# stm32_motordrive.net
KiCad netlist of a schematic drawn in EasyEDA Pro
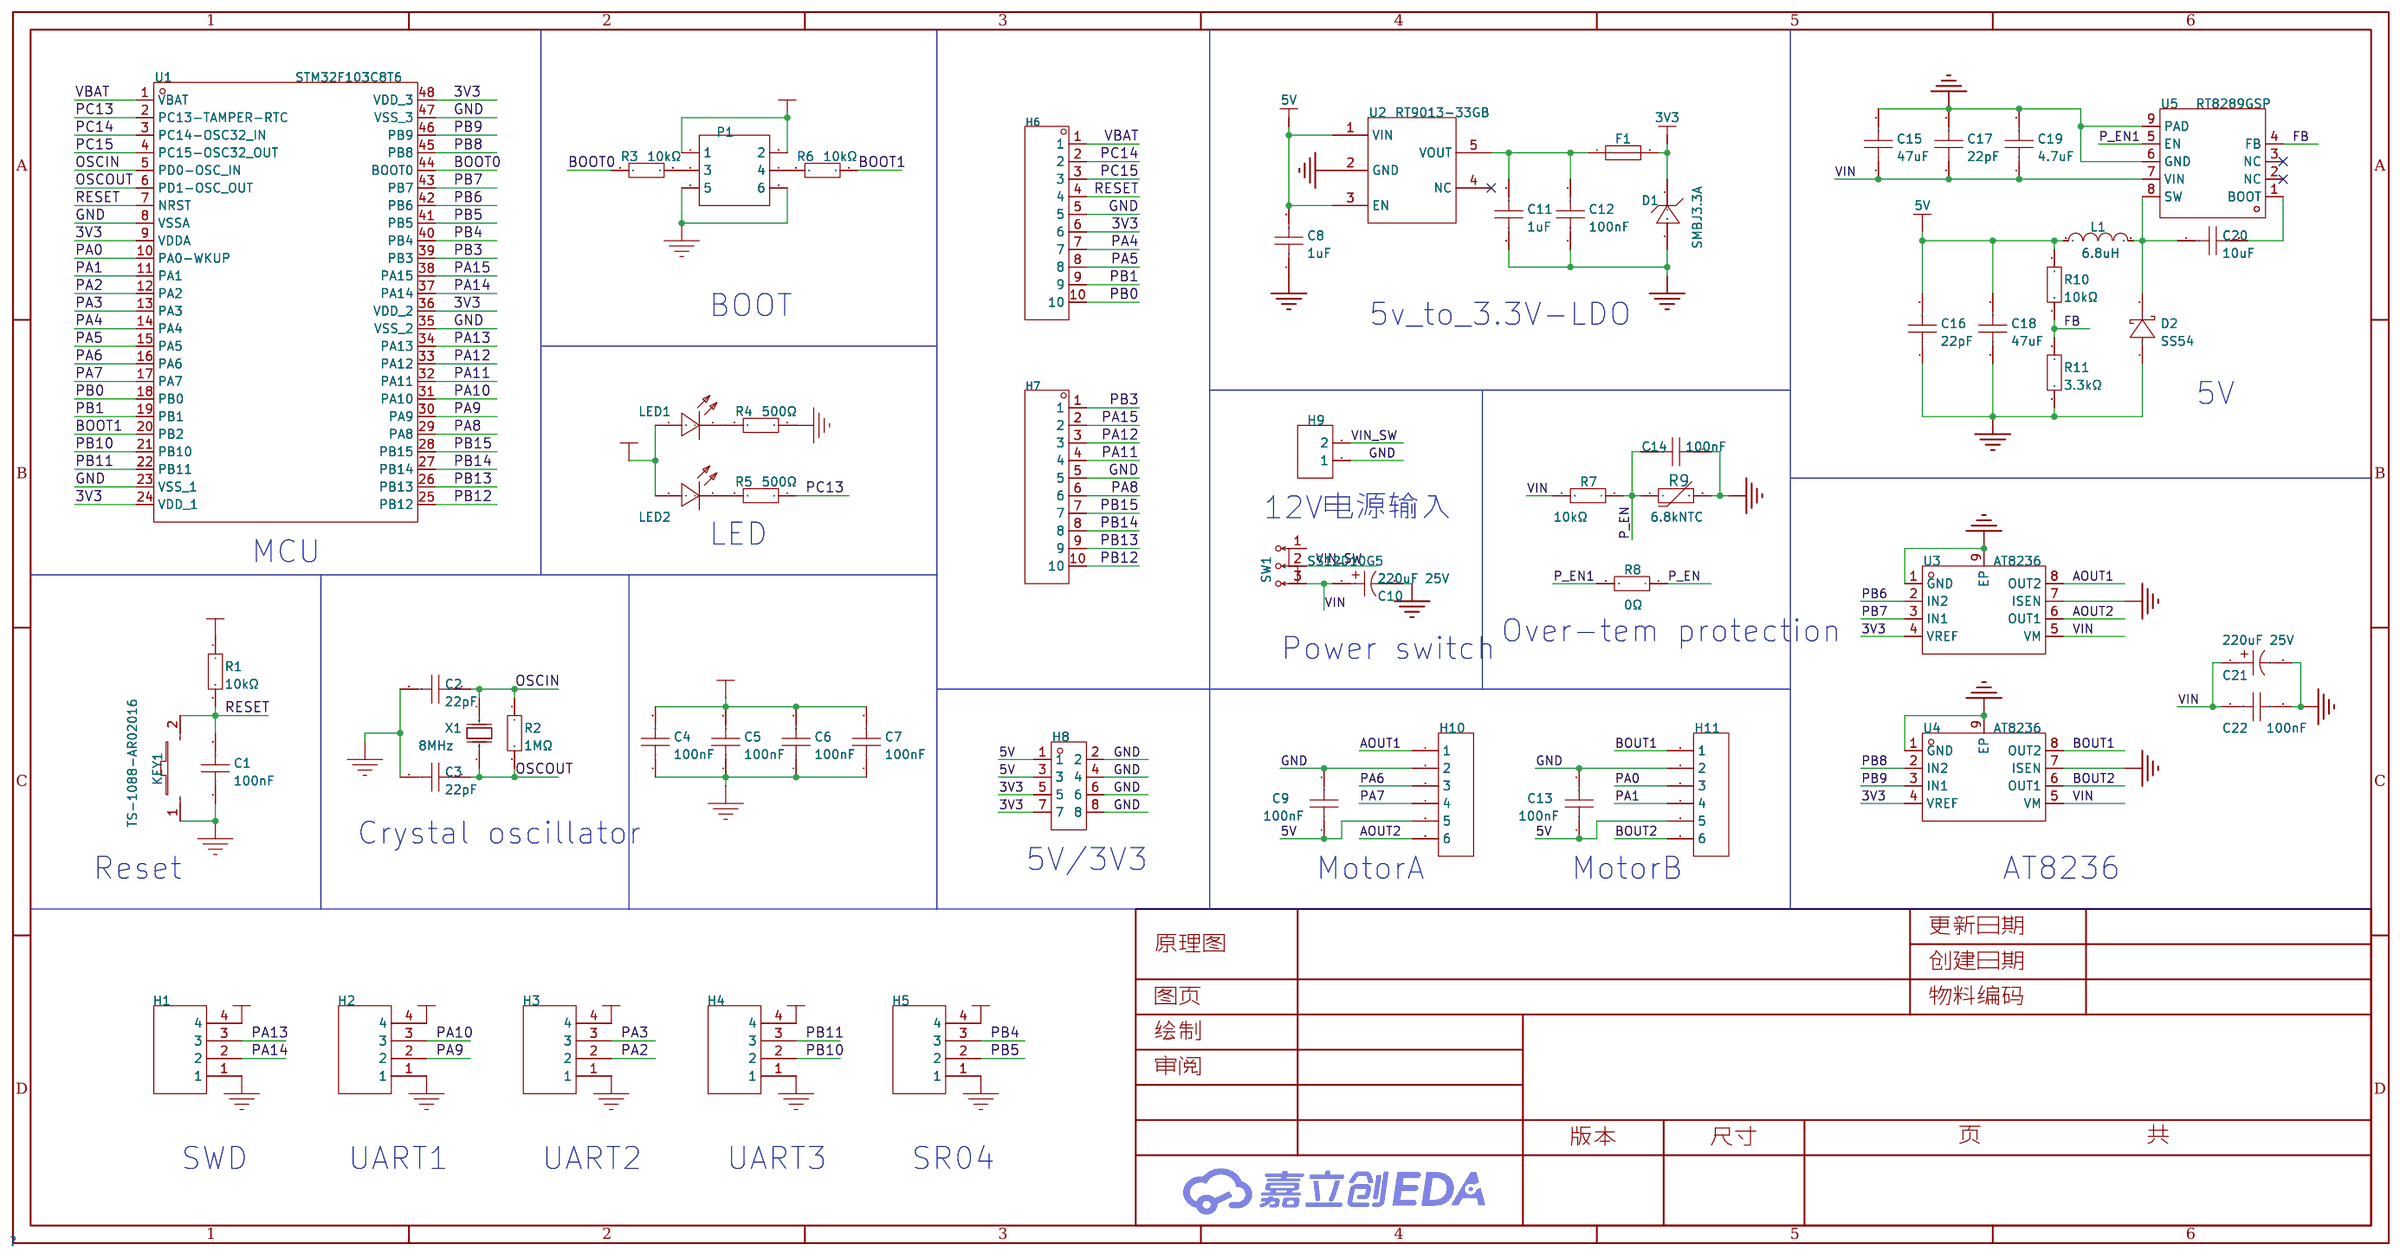
[diagram p0: schematic sheet]

(export (version "E")
  (design (tool "Eeschema 10.0.6"))
  (components
    (comp (ref "C1")
      (value "100nF")
      (fields
        (field (name "Manufacturer Part") "CC0603KRX7R9BB104")
        (field (name "Manufacturer") "YAGEO(国巨)")
      )
      (libsource (lib "easyedapro") (part "104"))
    )
    (comp (ref "C2")
      (value "22pF")
      (fields
        (field (name "Manufacturer Part") "CC0603JRNPO9BN220")
        (field (name "Manufacturer") "YAGEO(国巨)")
      )
      (libsource (lib "easyedapro") (part "22P"))
    )
    (comp (ref "C3")
      (value "22pF")
      (fields
        (field (name "Manufacturer Part") "CC0603JRNPO9BN220")
        (field (name "Manufacturer") "YAGEO(国巨)")
      )
      (libsource (lib "easyedapro") (part "22P"))
    )
    (comp (ref "C4")
      (value "100nF")
      (fields
        (field (name "Manufacturer Part") "CC0603KRX7R9BB104")
        (field (name "Manufacturer") "YAGEO(国巨)")
      )
      (libsource (lib "easyedapro") (part "104"))
    )
    (comp (ref "C5")
      (value "100nF")
      (fields
        (field (name "Manufacturer Part") "CC0603KRX7R9BB104")
        (field (name "Manufacturer") "YAGEO(国巨)")
      )
      (libsource (lib "easyedapro") (part "104"))
    )
    (comp (ref "C6")
      (value "100nF")
      (fields
        (field (name "Manufacturer Part") "CC0603KRX7R9BB104")
        (field (name "Manufacturer") "YAGEO(国巨)")
      )
      (libsource (lib "easyedapro") (part "104"))
    )
    (comp (ref "C7")
      (value "100nF")
      (fields
        (field (name "Manufacturer Part") "CC0603KRX7R9BB104")
        (field (name "Manufacturer") "YAGEO(国巨)")
      )
      (libsource (lib "easyedapro") (part "104"))
    )
    (comp (ref "C8")
      (value "1uF")
      (fields
        (field (name "Manufacturer Part") "CL10A105KB8NNNC")
        (field (name "Manufacturer") "SAMSUNG(三星)")
      )
      (libsource (lib "easyedapro") (part "CapAcitance"))
    )
    (comp (ref "C9")
      (value "100nF")
      (fields
        (field (name "Manufacturer Part") "CC0603KRX7R9BB104")
        (field (name "Manufacturer") "YAGEO(国巨)")
      )
      (libsource (lib "easyedapro") (part "CapAcitance"))
    )
    (comp (ref "C10")
      (value "220uF 25V")
      (footprint "easyedapro:CAP-SMD_BD6.3-L6.6-W6.6-LS7.2-FD")
      (description "容值:220uF;精度:±20%;额定电压:25V;纹波电流:165mA@120Hz;等效串联电阻:-;")
      (fields (field (name "Manufacturer Part") "RST220UF25V019") (field (name "Manufacturer") "KNSCHA(科尼盛)"))
      (libsource (lib "easyedapro") (part "RST220UF25V019"))
    )
    (comp (ref "C11")
      (value "1uF")
      (fields
        (field (name "Manufacturer Part") "CL10A105KB8NNNC")
        (field (name "Manufacturer") "SAMSUNG(三星)")
      )
      (libsource (lib "easyedapro") (part "CapAcitance"))
    )
    (comp (ref "C12")
      (value "100nF")
      (fields
        (field (name "Manufacturer Part") "CC0603KRX7R9BB104")
        (field (name "Manufacturer") "YAGEO(国巨)")
      )
      (libsource (lib "easyedapro") (part "CapAcitance"))
    )
    (comp (ref "C13")
      (value "100nF")
      (fields
        (field (name "Manufacturer Part") "CC0603KRX7R9BB104")
        (field (name "Manufacturer") "YAGEO(国巨)")
      )
      (libsource (lib "easyedapro") (part "CapAcitance"))
    )
    (comp (ref "C14")
      (value "100nF")
      (fields
        (field (name "Manufacturer Part") "CC0603KRX7R9BB104")
        (field (name "Manufacturer") "YAGEO(国巨)")
      )
      (libsource (lib "easyedapro") (part "CapAcitance"))
    )
    (comp (ref "C15")
      (value "47uF")
      (fields
        (field (name "Manufacturer Part") "CL10A476MQ8QRNC")
        (field (name "Manufacturer") "SAMSUNG(三星)")
      )
      (libsource (lib "easyedapro") (part "CapAcitance"))
    )
    (comp (ref "C16")
      (value "22pF")
      (fields
        (field (name "Manufacturer Part") "CC0603JRNPO9BN220")
        (field (name "Manufacturer") "YAGEO(国巨)")
      )
      (libsource (lib "easyedapro") (part "CapAcitance"))
    )
    (comp (ref "C17")
      (value "22pF")
      (fields
        (field (name "Manufacturer Part") "CC0603JRNPO9BN220")
        (field (name "Manufacturer") "YAGEO(国巨)")
      )
      (libsource (lib "easyedapro") (part "CapAcitance"))
    )
    (comp (ref "C18")
      (value "47uF")
      (fields
        (field (name "Manufacturer Part") "CL10A476MQ8QRNC")
        (field (name "Manufacturer") "SAMSUNG(三星)")
      )
      (libsource (lib "easyedapro") (part "CapAcitance"))
    )
    (comp (ref "C19")
      (value "4.7uF")
      (fields
        (field (name "Manufacturer Part") "CL10A475KP8NNNC")
        (field (name "Manufacturer") "SAMSUNG(三星)")
      )
      (libsource (lib "easyedapro") (part "CapAcitance"))
    )
    (comp (ref "C20")
      (value "10uF")
      (fields
        (field (name "Manufacturer Part") "CL10A106KP8NNNC")
        (field (name "Manufacturer") "SAMSUNG(三星)")
      )
      (libsource (lib "easyedapro") (part "CapAcitance"))
    )
    (comp (ref "C21")
      (value "220uF 25V")
      (footprint "easyedapro:CAP-SMD_BD6.3-L6.6-W6.6-LS7.2-FD")
      (description "容值:220uF;精度:±20%;额定电压:25V;纹波电流:165mA@120Hz;等效串联电阻:-;")
      (fields (field (name "Manufacturer Part") "RST220UF25V019") (field (name "Manufacturer") "KNSCHA(科尼盛)"))
      (libsource (lib "easyedapro") (part "RST220UF25V019"))
    )
    (comp (ref "C22")
      (value "100nF")
      (fields
        (field (name "Manufacturer Part") "CC0603KRX7R9BB104")
        (field (name "Manufacturer") "YAGEO(国巨)")
      )
      (libsource (lib "easyedapro") (part "CapAcitance"))
    )
    (comp (ref "D1")
      (value "SMBJ3.3A")
      (footprint "easyedapro:SMB_L4.6-W3.6-LS5.3-RD")
      (description "反向截止电压(Vrwm):3.3V;最大钳位电压:7.3V;峰值脉冲功率(Ppp)@10/1000us:600W;击穿电压:4.1V;")
      (fields (field (name "Manufacturer") "JKSEMI(金开盛)"))
      (libsource (lib "easyedapro") (part "SMBJ3.3A_C362089"))
    )
    (comp (ref "D2")
      (value "SS54")
      (footprint "easyedapro:SMA_L4.3-W2.6-LS5.0-FD")
      (description "二极管配置:独立式;正向压降(Vf):550mV@5.0A;直流反向耐压(Vr):40V;平均整流电流(Io):5A;")
      (fields (field (name "Manufacturer") "宏迦橙"))
      (libsource (lib "easyedapro") (part "SS54_C7420369"))
    )
    (comp (ref "F1")
      (value "BSMD0603-050-6V")
      (footprint "easyedapro:F0603")
      (description "最大电压:6V;最大电流:40A;保持电流:500mA;跳闸电流:1A;")
      (fields (field (name "Manufacturer") "BHFUSE(佰宏)"))
      (libsource (lib "easyedapro") (part "BSMD0603-050-6V"))
    )
    (comp (ref "H1")
      (value "PZ254V-11-04P")
      (fields (field (name "Manufacturer") "XFCN(兴飞)"))
      (libsource (lib "easyedapro") (part "220S-1*4P H=8.5MM Ytype Gold-plated"))
    )
    (comp (ref "H2")
      (value "PZ254V-11-04P")
      (fields (field (name "Manufacturer") "XFCN(兴飞)"))
      (libsource (lib "easyedapro") (part "220S-1*4P H=8.5MM Ytype Gold-plated"))
    )
    (comp (ref "H3")
      (value "PZ254V-11-04P")
      (fields (field (name "Manufacturer") "XFCN(兴飞)"))
      (libsource (lib "easyedapro") (part "220S-1*4P H=8.5MM Ytype Gold-plated"))
    )
    (comp (ref "H4")
      (value "PZ254V-11-04P")
      (fields (field (name "Manufacturer") "XFCN(兴飞)"))
      (libsource (lib "easyedapro") (part "220S-1*4P H=8.5MM Ytype Gold-plated"))
    )
    (comp (ref "H5")
      (value "PZ254V-11-04P")
      (fields (field (name "Manufacturer") "XFCN(兴飞)"))
      (libsource (lib "easyedapro") (part "220S-1*4P H=8.5MM Ytype Gold-plated"))
    )
    (comp (ref "H6")
      (value "2.54-1*10P针")
      (footprint "easyedapro:HDR-TH_10P-P2.54-V-M-1")
      (fields (field (name "Manufacturer") "BOOMELE(博穆精密)"))
      (libsource (lib "easyedapro") (part "Header-Male-2.54_1x10"))
    )
    (comp (ref "H7")
      (value "2.54-1*10P针")
      (footprint "easyedapro:HDR-TH_10P-P2.54-V-M-1")
      (fields (field (name "Manufacturer") "BOOMELE(博穆精密)"))
      (libsource (lib "easyedapro") (part "Header-Male-2.54_1x10"))
    )
    (comp (ref "H8")
      (value "PZ2.54-2*4")
      (footprint "easyedapro:HDR-TH_8P-P2.54-V-M-R2-C4-S2.54")
      (description "插针结构:2x4P;间距:2.54mm;排数:双排;总PIN位数:8P;")
      (fields (field (name "Manufacturer") "ZHOURI(洲日)"))
      (libsource (lib "easyedapro") (part "PZ2.54-2*4"))
    )
    (comp (ref "H9")
      (value "XY301V-A-5.0-2P")
      (fields (field (name "Manufacturer") "XINLAIYA(新莱亚)"))
      (libsource (lib "easyedapro") (part "Header-Female-2.54_1x2"))
    )
    (comp (ref "H10")
      (value "~")
      (footprint "easyedapro:XH2.54-LI-6P弯针")
      (libsource (lib "easyedapro") (part "XH2.54-LI-6P弯针"))
    )
    (comp (ref "H11")
      (value "~")
      (footprint "easyedapro:XH2.54-LI-6P弯针")
      (libsource (lib "easyedapro") (part "XH2.54-LI-6P弯针"))
    )
    (comp (ref "KEY1")
      (value "TS-1088-AR02016")
      (fields (field (name "Manufacturer") "XUNPU(讯普)"))
      (libsource (lib "easyedapro") (part "Switch3x4x2"))
    )
    (comp (ref "L1")
      (value "6.8uH")
      (fields (field (name "Manufacturer Part") "FXL0630-6R8-M") (field (name "Manufacturer") "cjiang(长江微电)"))
      (libsource (lib "easyedapro") (part "SDFL1608S100KTF"))
    )
    (comp (ref "LED1")
      (value "NCD0805R1")
      (fields (field (name "Manufacturer") "国星光电"))
      (libsource (lib "easyedapro") (part "204-10SURD/S530-A3"))
    )
    (comp (ref "LED2")
      (value "NCD0805R1")
      (fields (field (name "Manufacturer") "国星光电"))
      (libsource (lib "easyedapro") (part "204-10SURD/S530-A3"))
    )
    (comp (ref "P1")
      (value "2.54-2*3P针")
      (fields (field (name "Manufacturer") "BOOMELE(博穆精密)"))
      (libsource (lib "easyedapro") (part "HDR-IDC-2.54-2X3P"))
    )
    (comp (ref "R1")
      (value "10kΩ")
      (fields
        (field (name "Manufacturer Part") "0603WAF1002T5E")
        (field (name "Manufacturer") "UNI-ROYAL(厚声)")
      )
      (libsource (lib "easyedapro") (part "电阻"))
    )
    (comp (ref "R2")
      (value "1MΩ")
      (fields
        (field (name "Manufacturer Part") "0603WAF1004T5E")
        (field (name "Manufacturer") "UNI-ROYAL(厚声)")
      )
      (libsource (lib "easyedapro") (part "电阻"))
    )
    (comp (ref "R3")
      (value "10kΩ")
      (fields
        (field (name "Manufacturer Part") "0603WAF1002T5E")
        (field (name "Manufacturer") "UNI-ROYAL(厚声)")
      )
      (libsource (lib "easyedapro") (part "电阻"))
    )
    (comp (ref "R4")
      (value "500Ω")
      (fields (field (name "Manufacturer Part") "RT0603BRC07500RL") (field (name "Manufacturer") "YAGEO(国巨)"))
      (libsource (lib "easyedapro") (part "电阻"))
    )
    (comp (ref "R5")
      (value "500Ω")
      (fields (field (name "Manufacturer Part") "RT0603BRC07500RL") (field (name "Manufacturer") "YAGEO(国巨)"))
      (libsource (lib "easyedapro") (part "电阻"))
    )
    (comp (ref "R6")
      (value "10kΩ")
      (fields
        (field (name "Manufacturer Part") "0603WAF1002T5E")
        (field (name "Manufacturer") "UNI-ROYAL(厚声)")
      )
      (libsource (lib "easyedapro") (part "电阻"))
    )
    (comp (ref "R7")
      (value "10kΩ")
      (fields (field (name "Manufacturer Part") "RT0603BRD0710KL") (field (name "Manufacturer") "YAGEO(国巨)"))
      (libsource (lib "easyedapro") (part "电阻"))
    )
    (comp (ref "R8")
      (value "0Ω")
      (fields
        (field (name "Manufacturer Part") "0603WAF0000T5E")
        (field (name "Manufacturer") "UNI-ROYAL(厚声)")
      )
      (libsource (lib "easyedapro") (part "电阻"))
    )
    (comp (ref "R9")
      (value "6.8kNTC")
      (footprint "easyedapro:R0603")
      (description "阻值(25°C):6.8kΩ;B值(25°C/50°C):3950K;电阻精度:±5%;功率:100mW;B值精度:±3%;最大稳态电流(25°C):380uA;")
      (fields (field (name "Manufacturer") "muRata(村田)"))
      (libsource (lib "easyedapro") (part "NCP18XW682J03RB"))
    )
    (comp (ref "R10")
      (value "10kΩ")
      (fields (field (name "Manufacturer Part") "RT0603BRD0710KL") (field (name "Manufacturer") "YAGEO(国巨)"))
      (libsource (lib "easyedapro") (part "电阻"))
    )
    (comp (ref "R11")
      (value "3.3kΩ")
      (fields
        (field (name "Manufacturer Part") "0603WAF3301T5E")
        (field (name "Manufacturer") "UNI-ROYAL(厚声)")
      )
      (libsource (lib "easyedapro") (part "电阻"))
    )
    (comp (ref "SW1")
      (value "SS12D10G5")
      (fields (field (name "Manufacturer") "SHOU HAN(首韩)"))
      (libsource (lib "easyedapro") (part "3脚两档开关(SS12D10G4型号）"))
    )
    (comp (ref "U1")
      (value "STM32F103C8T6")
      (fields (field (name "Manufacturer") "ST(意法半导体)"))
      (libsource (lib "easyedapro") (part "STM32F103C8T6"))
    )
    (comp (ref "U2")
      (value "RT9013-33GB")
      (footprint "easyedapro:SOT-23-5_L3.0-W1.7-P0.95-LS2.8-BL")
      (description "输出类型:固定;最大输入电压:5.5V;输出电压:3.3V;最大输出电流:500mA;电源纹波抑制比(PSRR):50dB@(10kHz);输出极性:正极;")
      (fields (field (name "Manufacturer") "RICHTEK(立锜)"))
      (libsource (lib "easyedapro") (part "RT9013-33GB"))
    )
    (comp (ref "U3")
      (value "AT8236")
      (footprint "easyedapro:ESOP-8_L4.9-W3.9-P1.27-LS6.0-BL-EP")
      (fields (field (name "Manufacturer") "杭州中科微"))
      (libsource (lib "easyedapro") (part "AT8236"))
    )
    (comp (ref "U4")
      (value "AT8236")
      (footprint "easyedapro:ESOP-8_L4.9-W3.9-P1.27-LS6.0-BL-EP")
      (fields (field (name "Manufacturer") "杭州中科微"))
      (libsource (lib "easyedapro") (part "AT8236"))
    )
    (comp (ref "U5")
      (value "RT8289GSP")
      (footprint "easyedapro:SOIC-8_L5.0-W4.0-P1.27-LS6.0-BL-EP2.0")
      (description "功能类型:降压型;输出类型:可调;输入电压:5.5V~32V;输出电压:1.222V~26V;输出电流(最大值):5A;")
      (fields (field (name "Manufacturer") "RICHTEK(立锜)"))
      (libsource (lib "easyedapro") (part "RT8289GSP"))
    )
    (comp (ref "X1")
      (value "8MHz")
      (fields (field (name "Manufacturer Part") "X50328MSB2GI") (field (name "Manufacturer") "YXC(扬兴晶振)"))
      (libsource (lib "easyedapro") (part "8MHz"))
    )
  )
  (nets
    (net (code "1") (name "/AOUT1") (class "Default")
      (node (ref "H10") (pin "1") (pinfunction "1_1") (pintype "input"))
      (node (ref "U3") (pin "8") (pinfunction "OUT2_8") (pintype "unspecified"))
    )
    (net (code "2") (name "/AOUT2") (class "Default")
      (node (ref "H10") (pin "6") (pinfunction "6_6") (pintype "input"))
      (node (ref "U3") (pin "6") (pinfunction "OUT1_6") (pintype "unspecified"))
    )
    (net (code "3") (name "/BOOT0") (class "Default")
      (node (ref "R3") (pin "2") (pinfunction "2_2") (pintype "input"))
      (node (ref "U1") (pin "44") (pinfunction "BOOT0_44") (pintype "unspecified"))
    )
    (net (code "4") (name "/BOOT1") (class "Default")
      (node (ref "R6") (pin "1") (pinfunction "1_1") (pintype "input"))
      (node (ref "U1") (pin "20") (pinfunction "PB2_20") (pintype "unspecified"))
    )
    (net (code "5") (name "/BOUT1") (class "Default")
      (node (ref "H11") (pin "1") (pinfunction "1_1") (pintype "input"))
      (node (ref "U4") (pin "8") (pinfunction "OUT2_8") (pintype "unspecified"))
    )
    (net (code "6") (name "/BOUT2") (class "Default")
      (node (ref "H11") (pin "6") (pinfunction "6_6") (pintype "input"))
      (node (ref "U4") (pin "6") (pinfunction "OUT1_6") (pintype "unspecified"))
    )
    (net (code "7") (name "/FB") (class "Default")
      (node (ref "R10") (pin "1") (pinfunction "1_1") (pintype "input"))
      (node (ref "R11") (pin "2") (pinfunction "2_2") (pintype "input"))
      (node (ref "U5") (pin "4") (pinfunction "FB_4") (pintype "unspecified"))
    )
    (net (code "8") (name "/OSCIN") (class "Default")
      (node (ref "C2") (pin "1") (pinfunction "1_1") (pintype "unspecified"))
      (node (ref "R2") (pin "1") (pinfunction "1_1") (pintype "input"))
      (node (ref "U1") (pin "5") (pinfunction "PD0-OSC_IN_5") (pintype "unspecified"))
      (node (ref "X1") (pin "1") (pinfunction "OSC1_1") (pintype "unspecified"))
    )
    (net (code "9") (name "/OSCOUT") (class "Default")
      (node (ref "C3") (pin "1") (pinfunction "1_1") (pintype "unspecified"))
      (node (ref "R2") (pin "2") (pinfunction "2_2") (pintype "input"))
      (node (ref "U1") (pin "6") (pinfunction "PD1-OSC_OUT_6") (pintype "unspecified"))
      (node (ref "X1") (pin "2") (pinfunction "OSC2_2") (pintype "unspecified"))
    )
    (net (code "10") (name "/PA0") (class "Default")
      (node (ref "H11") (pin "3") (pinfunction "3_3") (pintype "input"))
      (node (ref "U1") (pin "10") (pinfunction "PA0-WKUP_10") (pintype "unspecified"))
    )
    (net (code "11") (name "/PA1") (class "Default")
      (node (ref "H11") (pin "4") (pinfunction "4_4") (pintype "input"))
      (node (ref "U1") (pin "11") (pinfunction "PA1_11") (pintype "unspecified"))
    )
    (net (code "12") (name "/PA2") (class "Default")
      (node (ref "H3") (pin "2") (pinfunction "2_2") (pintype "unspecified"))
      (node (ref "U1") (pin "12") (pinfunction "PA2_12") (pintype "unspecified"))
    )
    (net (code "13") (name "/PA3") (class "Default")
      (node (ref "H3") (pin "3") (pinfunction "3_3") (pintype "unspecified"))
      (node (ref "U1") (pin "13") (pinfunction "PA3_13") (pintype "unspecified"))
    )
    (net (code "14") (name "/PA4") (class "Default")
      (node (ref "H6") (pin "7") (pinfunction "7_7") (pintype "input"))
      (node (ref "U1") (pin "14") (pinfunction "PA4_14") (pintype "unspecified"))
    )
    (net (code "15") (name "/PA5") (class "Default")
      (node (ref "H6") (pin "8") (pinfunction "8_8") (pintype "input"))
      (node (ref "U1") (pin "15") (pinfunction "PA5_15") (pintype "unspecified"))
    )
    (net (code "16") (name "/PA6") (class "Default")
      (node (ref "H10") (pin "3") (pinfunction "3_3") (pintype "input"))
      (node (ref "U1") (pin "16") (pinfunction "PA6_16") (pintype "unspecified"))
    )
    (net (code "17") (name "/PA7") (class "Default")
      (node (ref "H10") (pin "4") (pinfunction "4_4") (pintype "input"))
      (node (ref "U1") (pin "17") (pinfunction "PA7_17") (pintype "unspecified"))
    )
    (net (code "18") (name "/PA8") (class "Default")
      (node (ref "H7") (pin "6") (pinfunction "6_6") (pintype "input"))
      (node (ref "U1") (pin "29") (pinfunction "PA8_29") (pintype "unspecified"))
    )
    (net (code "19") (name "/PA9") (class "Default")
      (node (ref "H2") (pin "2") (pinfunction "2_2") (pintype "unspecified"))
      (node (ref "U1") (pin "30") (pinfunction "PA9_30") (pintype "unspecified"))
    )
    (net (code "20") (name "/PA10") (class "Default")
      (node (ref "H2") (pin "3") (pinfunction "3_3") (pintype "unspecified"))
      (node (ref "U1") (pin "31") (pinfunction "PA10_31") (pintype "unspecified"))
    )
    (net (code "21") (name "/PA11") (class "Default")
      (node (ref "H7") (pin "4") (pinfunction "4_4") (pintype "input"))
      (node (ref "U1") (pin "32") (pinfunction "PA11_32") (pintype "unspecified"))
    )
    (net (code "22") (name "/PA12") (class "Default")
      (node (ref "H7") (pin "3") (pinfunction "3_3") (pintype "input"))
      (node (ref "U1") (pin "33") (pinfunction "PA12_33") (pintype "unspecified"))
    )
    (net (code "23") (name "/PA13") (class "Default")
      (node (ref "H1") (pin "3") (pinfunction "3_3") (pintype "unspecified"))
      (node (ref "U1") (pin "34") (pinfunction "PA13_34") (pintype "unspecified"))
    )
    (net (code "24") (name "/PA14") (class "Default")
      (node (ref "H1") (pin "2") (pinfunction "2_2") (pintype "unspecified"))
      (node (ref "U1") (pin "37") (pinfunction "PA14_37") (pintype "unspecified"))
    )
    (net (code "25") (name "/PA15") (class "Default")
      (node (ref "H7") (pin "2") (pinfunction "2_2") (pintype "input"))
      (node (ref "U1") (pin "38") (pinfunction "PA15_38") (pintype "unspecified"))
    )
    (net (code "26") (name "/PB0") (class "Default")
      (node (ref "H6") (pin "10") (pinfunction "10_10") (pintype "input"))
      (node (ref "U1") (pin "18") (pinfunction "PB0_18") (pintype "unspecified"))
    )
    (net (code "27") (name "/PB1") (class "Default")
      (node (ref "H6") (pin "9") (pinfunction "9_9") (pintype "input"))
      (node (ref "U1") (pin "19") (pinfunction "PB1_19") (pintype "unspecified"))
    )
    (net (code "28") (name "/PB3") (class "Default")
      (node (ref "H7") (pin "1") (pinfunction "1_1") (pintype "input"))
      (node (ref "U1") (pin "39") (pinfunction "PB3_39") (pintype "unspecified"))
    )
    (net (code "29") (name "/PB4") (class "Default")
      (node (ref "H5") (pin "3") (pinfunction "3_3") (pintype "unspecified"))
      (node (ref "U1") (pin "40") (pinfunction "PB4_40") (pintype "unspecified"))
    )
    (net (code "30") (name "/PB5") (class "Default")
      (node (ref "H5") (pin "2") (pinfunction "2_2") (pintype "unspecified"))
      (node (ref "U1") (pin "41") (pinfunction "PB5_41") (pintype "unspecified"))
    )
    (net (code "31") (name "/PB6") (class "Default")
      (node (ref "U1") (pin "42") (pinfunction "PB6_42") (pintype "unspecified"))
      (node (ref "U3") (pin "2") (pinfunction "IN2_2") (pintype "unspecified"))
    )
    (net (code "32") (name "/PB7") (class "Default")
      (node (ref "U1") (pin "43") (pinfunction "PB7_43") (pintype "unspecified"))
      (node (ref "U3") (pin "3") (pinfunction "IN1_3") (pintype "unspecified"))
    )
    (net (code "33") (name "/PB8") (class "Default")
      (node (ref "U1") (pin "45") (pinfunction "PB8_45") (pintype "unspecified"))
      (node (ref "U4") (pin "2") (pinfunction "IN2_2") (pintype "unspecified"))
    )
    (net (code "34") (name "/PB9") (class "Default")
      (node (ref "U1") (pin "46") (pinfunction "PB9_46") (pintype "unspecified"))
      (node (ref "U4") (pin "3") (pinfunction "IN1_3") (pintype "unspecified"))
    )
    (net (code "35") (name "/PB10") (class "Default")
      (node (ref "H4") (pin "2") (pinfunction "2_2") (pintype "unspecified"))
      (node (ref "U1") (pin "21") (pinfunction "PB10_21") (pintype "unspecified"))
    )
    (net (code "36") (name "/PB11") (class "Default")
      (node (ref "H4") (pin "3") (pinfunction "3_3") (pintype "unspecified"))
      (node (ref "U1") (pin "22") (pinfunction "PB11_22") (pintype "unspecified"))
    )
    (net (code "37") (name "/PB12") (class "Default")
      (node (ref "H7") (pin "10") (pinfunction "10_10") (pintype "input"))
      (node (ref "U1") (pin "25") (pinfunction "PB12_25") (pintype "unspecified"))
    )
    (net (code "38") (name "/PB13") (class "Default")
      (node (ref "H7") (pin "9") (pinfunction "9_9") (pintype "input"))
      (node (ref "U1") (pin "26") (pinfunction "PB13_26") (pintype "unspecified"))
    )
    (net (code "39") (name "/PB14") (class "Default")
      (node (ref "H7") (pin "8") (pinfunction "8_8") (pintype "input"))
      (node (ref "U1") (pin "27") (pinfunction "PB14_27") (pintype "unspecified"))
    )
    (net (code "40") (name "/PB15") (class "Default")
      (node (ref "H7") (pin "7") (pinfunction "7_7") (pintype "input"))
      (node (ref "U1") (pin "28") (pinfunction "PB15_28") (pintype "unspecified"))
    )
    (net (code "41") (name "/PC13") (class "Default")
      (node (ref "R5") (pin "1") (pinfunction "1_1") (pintype "input"))
      (node (ref "U1") (pin "2") (pinfunction "PC13-TAMPER-RTC_2") (pintype "unspecified"))
    )
    (net (code "42") (name "/PC14") (class "Default")
      (node (ref "H6") (pin "2") (pinfunction "2_2") (pintype "input"))
      (node (ref "U1") (pin "3") (pinfunction "PC14-OSC32_IN_3") (pintype "unspecified"))
    )
    (net (code "43") (name "/PC15") (class "Default")
      (node (ref "H6") (pin "3") (pinfunction "3_3") (pintype "input"))
      (node (ref "U1") (pin "4") (pinfunction "PC15-OSC32_OUT_4") (pintype "unspecified"))
    )
    (net (code "44") (name "/P_EN") (class "Default")
      (node (ref "C14") (pin "2") (pinfunction "2_2") (pintype "input"))
      (node (ref "R7") (pin "1") (pinfunction "1_1") (pintype "input"))
      (node (ref "R8") (pin "1") (pinfunction "1_1") (pintype "input"))
      (node (ref "R9") (pin "1") (pinfunction "1_1") (pintype "input"))
    )
    (net (code "45") (name "/P_EN1") (class "Default")
      (node (ref "R8") (pin "2") (pinfunction "2_2") (pintype "input"))
      (node (ref "U5") (pin "5") (pinfunction "EN_5") (pintype "unspecified"))
    )
    (net (code "46") (name "/RESET") (class "Default")
      (node (ref "C1") (pin "2") (pinfunction "2_2") (pintype "unspecified"))
      (node (ref "H6") (pin "4") (pinfunction "4_4") (pintype "input"))
      (node (ref "KEY1") (pin "2") (pinfunction "2_2") (pintype "unspecified"))
      (node (ref "R1") (pin "2") (pinfunction "2_2") (pintype "input"))
      (node (ref "U1") (pin "7") (pinfunction "NRST_7") (pintype "unspecified"))
    )
    (net (code "47") (name "/VBAT") (class "Default")
      (node (ref "H6") (pin "1") (pinfunction "1_1") (pintype "input"))
      (node (ref "U1") (pin "1") (pinfunction "VBAT_1") (pintype "unspecified"))
    )
    (net (code "48") (name "/VIN") (class "Default")
      (node (ref "C10") (pin "1") (pinfunction "1_1") (pintype "input"))
      (node (ref "C15") (pin "1") (pinfunction "1_1") (pintype "input"))
      (node (ref "C17") (pin "1") (pinfunction "1_1") (pintype "input"))
      (node (ref "C19") (pin "1") (pinfunction "1_1") (pintype "input"))
      (node (ref "C21") (pin "1") (pinfunction "1_1") (pintype "input"))
      (node (ref "C22") (pin "2") (pinfunction "2_2") (pintype "input"))
      (node (ref "R7") (pin "2") (pinfunction "2_2") (pintype "input"))
      (node (ref "SW1") (pin "3") (pinfunction "3_3") (pintype "input"))
      (node (ref "U3") (pin "5") (pinfunction "VM_5") (pintype "unspecified"))
      (node (ref "U4") (pin "5") (pinfunction "VM_5") (pintype "unspecified"))
      (node (ref "U5") (pin "7") (pinfunction "VIN_7") (pintype "unspecified"))
    )
    (net (code "49") (name "/VIN_SW") (class "Default")
      (node (ref "H9") (pin "2") (pinfunction "2_2") (pintype "input"))
      (node (ref "SW1") (pin "2") (pinfunction "2_2") (pintype "input"))
    )
    (net (code "50") (name "3V3") (class "Default")
      (node (ref "C4") (pin "2") (pinfunction "2_2") (pintype "unspecified"))
      (node (ref "C5") (pin "2") (pinfunction "2_2") (pintype "unspecified"))
      (node (ref "C6") (pin "2") (pinfunction "2_2") (pintype "unspecified"))
      (node (ref "C7") (pin "2") (pinfunction "2_2") (pintype "unspecified"))
      (node (ref "D1") (pin "1") (pinfunction "1_1") (pintype "input"))
      (node (ref "F1") (pin "2") (pinfunction "2_2") (pintype "unspecified"))
      (node (ref "H6") (pin "6") (pinfunction "6_6") (pintype "input"))
      (node (ref "H8") (pin "5") (pinfunction "5_5") (pintype "unspecified"))
      (node (ref "H8") (pin "7") (pinfunction "7_7") (pintype "unspecified"))
      (node (ref "LED1") (pin "1") (pinfunction "A_1") (pintype "unspecified"))
      (node (ref "LED2") (pin "1") (pinfunction "A_1") (pintype "unspecified"))
      (node (ref "P1") (pin "1") (pinfunction "1_1") (pintype "unspecified"))
      (node (ref "P1") (pin "2") (pinfunction "2_2") (pintype "unspecified"))
      (node (ref "R1") (pin "1") (pinfunction "1_1") (pintype "input"))
      (node (ref "U1") (pin "24") (pinfunction "VDD_1_24") (pintype "unspecified"))
      (node (ref "U1") (pin "36") (pinfunction "VDD_2_36") (pintype "unspecified"))
      (node (ref "U1") (pin "48") (pinfunction "VDD_3_48") (pintype "unspecified"))
      (node (ref "U1") (pin "9") (pinfunction "VDDA_9") (pintype "unspecified"))
      (node (ref "U3") (pin "4") (pinfunction "VREF_4") (pintype "unspecified"))
      (node (ref "U4") (pin "4") (pinfunction "VREF_4") (pintype "unspecified"))
    )
    (net (code "51") (name "5V") (class "Default")
      (node (ref "C13") (pin "1") (pinfunction "1_1") (pintype "input"))
      (node (ref "C16") (pin "2") (pinfunction "2_2") (pintype "input"))
      (node (ref "C18") (pin "2") (pinfunction "2_2") (pintype "input"))
      (node (ref "C8") (pin "2") (pinfunction "2_2") (pintype "input"))
      (node (ref "C9") (pin "1") (pinfunction "1_1") (pintype "input"))
      (node (ref "H1") (pin "4") (pinfunction "4_4") (pintype "unspecified"))
      (node (ref "H10") (pin "5") (pinfunction "5_5") (pintype "input"))
      (node (ref "H11") (pin "5") (pinfunction "5_5") (pintype "input"))
      (node (ref "H2") (pin "4") (pinfunction "4_4") (pintype "unspecified"))
      (node (ref "H3") (pin "4") (pinfunction "4_4") (pintype "unspecified"))
      (node (ref "H4") (pin "4") (pinfunction "4_4") (pintype "unspecified"))
      (node (ref "H5") (pin "4") (pinfunction "4_4") (pintype "unspecified"))
      (node (ref "H8") (pin "1") (pinfunction "1_1") (pintype "unspecified"))
      (node (ref "H8") (pin "3") (pinfunction "3_3") (pintype "unspecified"))
      (node (ref "L1") (pin "1") (pinfunction "1_1") (pintype "unspecified"))
      (node (ref "R10") (pin "2") (pinfunction "2_2") (pintype "input"))
      (node (ref "U2") (pin "1") (pinfunction "VIN_1") (pintype "unspecified"))
      (node (ref "U2") (pin "3") (pinfunction "EN_3") (pintype "unspecified"))
    )
    (net (code "52") (name "GND") (class "Default")
      (node (ref "C1") (pin "1") (pinfunction "1_1") (pintype "unspecified"))
      (node (ref "C10") (pin "2") (pinfunction "2_2") (pintype "input"))
      (node (ref "C11") (pin "1") (pinfunction "1_1") (pintype "input"))
      (node (ref "C12") (pin "1") (pinfunction "1_1") (pintype "input"))
      (node (ref "C13") (pin "2") (pinfunction "2_2") (pintype "input"))
      (node (ref "C14") (pin "1") (pinfunction "1_1") (pintype "input"))
      (node (ref "C15") (pin "2") (pinfunction "2_2") (pintype "input"))
      (node (ref "C16") (pin "1") (pinfunction "1_1") (pintype "input"))
      (node (ref "C17") (pin "2") (pinfunction "2_2") (pintype "input"))
      (node (ref "C18") (pin "1") (pinfunction "1_1") (pintype "input"))
      (node (ref "C19") (pin "2") (pinfunction "2_2") (pintype "input"))
      (node (ref "C2") (pin "2") (pinfunction "2_2") (pintype "unspecified"))
      (node (ref "C21") (pin "2") (pinfunction "2_2") (pintype "input"))
      (node (ref "C22") (pin "1") (pinfunction "1_1") (pintype "input"))
      (node (ref "C3") (pin "2") (pinfunction "2_2") (pintype "unspecified"))
      (node (ref "C4") (pin "1") (pinfunction "1_1") (pintype "unspecified"))
      (node (ref "C5") (pin "1") (pinfunction "1_1") (pintype "unspecified"))
      (node (ref "C6") (pin "1") (pinfunction "1_1") (pintype "unspecified"))
      (node (ref "C7") (pin "1") (pinfunction "1_1") (pintype "unspecified"))
      (node (ref "C8") (pin "1") (pinfunction "1_1") (pintype "input"))
      (node (ref "C9") (pin "2") (pinfunction "2_2") (pintype "input"))
      (node (ref "D1") (pin "2") (pinfunction "2_2") (pintype "input"))
      (node (ref "D2") (pin "1") (pinfunction "A_1") (pintype "unspecified"))
      (node (ref "H1") (pin "1") (pinfunction "1_1") (pintype "unspecified"))
      (node (ref "H10") (pin "2") (pinfunction "2_2") (pintype "input"))
      (node (ref "H11") (pin "2") (pinfunction "2_2") (pintype "input"))
      (node (ref "H2") (pin "1") (pinfunction "1_1") (pintype "unspecified"))
      (node (ref "H3") (pin "1") (pinfunction "1_1") (pintype "unspecified"))
      (node (ref "H4") (pin "1") (pinfunction "1_1") (pintype "unspecified"))
      (node (ref "H5") (pin "1") (pinfunction "1_1") (pintype "unspecified"))
      (node (ref "H6") (pin "5") (pinfunction "5_5") (pintype "input"))
      (node (ref "H7") (pin "5") (pinfunction "5_5") (pintype "input"))
      (node (ref "H8") (pin "2") (pinfunction "2_2") (pintype "unspecified"))
      (node (ref "H8") (pin "4") (pinfunction "4_4") (pintype "unspecified"))
      (node (ref "H8") (pin "6") (pinfunction "6_6") (pintype "unspecified"))
      (node (ref "H8") (pin "8") (pinfunction "8_8") (pintype "unspecified"))
      (node (ref "H9") (pin "1") (pinfunction "1_1") (pintype "input"))
      (node (ref "KEY1") (pin "1") (pinfunction "1_1") (pintype "unspecified"))
      (node (ref "P1") (pin "5") (pinfunction "5_5") (pintype "unspecified"))
      (node (ref "P1") (pin "6") (pinfunction "6_6") (pintype "unspecified"))
      (node (ref "R11") (pin "1") (pinfunction "1_1") (pintype "input"))
      (node (ref "R4") (pin "1") (pinfunction "1_1") (pintype "input"))
      (node (ref "R9") (pin "2") (pinfunction "2_2") (pintype "input"))
      (node (ref "U1") (pin "23") (pinfunction "VSS_1_23") (pintype "unspecified"))
      (node (ref "U1") (pin "35") (pinfunction "VSS_2_35") (pintype "unspecified"))
      (node (ref "U1") (pin "47") (pinfunction "VSS_3_47") (pintype "unspecified"))
      (node (ref "U1") (pin "8") (pinfunction "VSSA_8") (pintype "unspecified"))
      (node (ref "U2") (pin "2") (pinfunction "GND_2") (pintype "unspecified"))
      (node (ref "U3") (pin "1") (pinfunction "GND_1") (pintype "unspecified"))
      (node (ref "U3") (pin "7") (pinfunction "ISEN_7") (pintype "unspecified"))
      (node (ref "U3") (pin "9") (pinfunction "EP_9") (pintype "unspecified"))
      (node (ref "U4") (pin "1") (pinfunction "GND_1") (pintype "unspecified"))
      (node (ref "U4") (pin "7") (pinfunction "ISEN_7") (pintype "unspecified"))
      (node (ref "U4") (pin "9") (pinfunction "EP_9") (pintype "unspecified"))
      (node (ref "U5") (pin "6") (pinfunction "GND_6") (pintype "unspecified"))
      (node (ref "U5") (pin "9") (pinfunction "PAD_9") (pintype "unspecified"))
    )
    (net (code "53") (name "Net-(D2-K)") (class "Default")
      (node (ref "C20") (pin "1") (pinfunction "1_1") (pintype "input"))
      (node (ref "D2") (pin "2") (pinfunction "K_2") (pintype "unspecified"))
      (node (ref "L1") (pin "2") (pinfunction "2_2") (pintype "unspecified"))
      (node (ref "U5") (pin "8") (pinfunction "SW_8") (pintype "unspecified"))
    )
    (net (code "54") (name "Net-(LED1-K)") (class "Default")
      (node (ref "LED1") (pin "2") (pinfunction "K_2") (pintype "unspecified"))
      (node (ref "R4") (pin "2") (pinfunction "2_2") (pintype "input"))
    )
    (net (code "55") (name "Net-(LED2-K)") (class "Default")
      (node (ref "LED2") (pin "2") (pinfunction "K_2") (pintype "unspecified"))
      (node (ref "R5") (pin "2") (pinfunction "2_2") (pintype "input"))
    )
    (net (code "56") (name "Net-(P1-Pad3)") (class "Default")
      (node (ref "P1") (pin "3") (pinfunction "3_3") (pintype "unspecified"))
      (node (ref "R3") (pin "1") (pinfunction "1_1") (pintype "input"))
    )
    (net (code "57") (name "Net-(P1-Pad4)") (class "Default")
      (node (ref "P1") (pin "4") (pinfunction "4_4") (pintype "unspecified"))
      (node (ref "R6") (pin "2") (pinfunction "2_2") (pintype "input"))
    )
    (net (code "58") (name "Net-(U2-VOUT)") (class "Default")
      (node (ref "C11") (pin "2") (pinfunction "2_2") (pintype "input"))
      (node (ref "C12") (pin "2") (pinfunction "2_2") (pintype "input"))
      (node (ref "F1") (pin "1") (pinfunction "1_1") (pintype "unspecified"))
      (node (ref "U2") (pin "5") (pinfunction "VOUT_5") (pintype "unspecified"))
    )
    (net (code "59") (name "Net-(U5-BOOT)") (class "Default")
      (node (ref "C20") (pin "2") (pinfunction "2_2") (pintype "input"))
      (node (ref "U5") (pin "1") (pinfunction "BOOT_1") (pintype "unspecified"))
    )
    (net (code "60") (name "unconnected-(SW1-Pad1)") (class "Default")
      (node (ref "SW1") (pin "1") (pinfunction "1_1") (pintype "input"))
    )
    (net (code "61") (name "unconnected-(U2-NC-Pad4)") (class "Default")
      (node (ref "U2") (pin "4") (pinfunction "NC_4") (pintype "unspecified+no_connect"))
    )
    (net (code "62") (name "unconnected-(U5-NC-Pad2)") (class "Default")
      (node (ref "U5") (pin "2") (pinfunction "NC_2") (pintype "unspecified+no_connect"))
    )
    (net (code "63") (name "unconnected-(U5-NC-Pad3)") (class "Default")
      (node (ref "U5") (pin "3") (pinfunction "NC_3") (pintype "unspecified+no_connect"))
    )
  )
)
